# 03_Mechanicals.net
KiCad netlist of a schematic drawn in Altium Designer
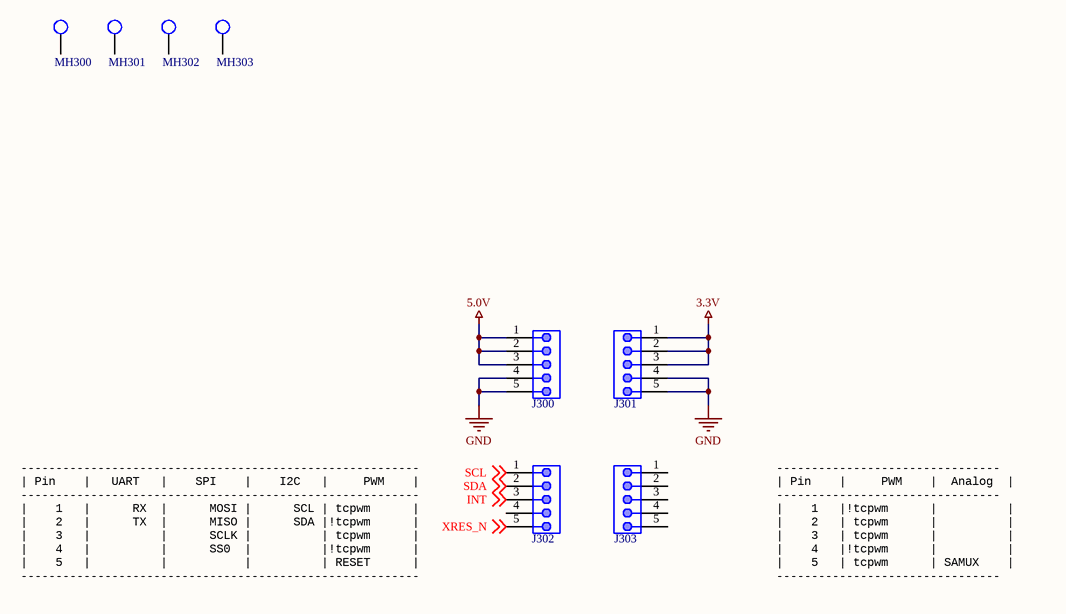
[diagram p0: 03_Mechanicals.SchDoc]

(export (version "E")
  (design (tool "Eeschema 10.0.6"))
  (components
    (comp (ref "J300")
      (value "CONN_HEADER_MALE_1x5")
      (footprint "HDR1X5")
      (description "Header, 5-Pin")
      (libsource (lib "Connectors") (part "CONN_HEADER_MALE_1x5"))
    )
    (comp (ref "J301")
      (value "CONN_HEADER_MALE_1x5")
      (footprint "HDR1X5")
      (description "Header, 5-Pin")
      (libsource (lib "") (part "CONN_HEADER_MALE_1x5_1"))
    )
    (comp (ref "J302")
      (value "CONN_HEADER_MALE_1x5")
      (footprint "HDR1X5")
      (description "Header, 5-Pin")
      (libsource (lib "Connectors") (part "CONN_HEADER_MALE_1x5"))
    )
    (comp (ref "J303")
      (value "CONN_HEADER_MALE_1x5")
      (footprint "HDR1X5")
      (description "Header, 5-Pin")
      (libsource (lib "") (part "CONN_HEADER_MALE_1x5_1"))
    )
    (comp (ref "MH300")
      (value "MHOLE_2_55MM")
      (footprint "MHOLE_2_55MM")
      (description "Mounting Holde")
      (fields (field (name "MANUFACTURER PART NUMBER") "UW MTHOLE"))
      (libsource (lib "ece315-2018-fall") (part "MHOLE_2_55MM"))
    )
    (comp (ref "MH301")
      (value "MHOLE_2_55MM")
      (footprint "MHOLE_2_55MM")
      (description "Mounting Holde")
      (fields (field (name "MANUFACTURER PART NUMBER") "UW MTHOLE"))
      (libsource (lib "ece315-2018-fall") (part "MHOLE_2_55MM"))
    )
    (comp (ref "MH302")
      (value "MHOLE_2_55MM")
      (footprint "MHOLE_2_55MM")
      (description "Mounting Holde")
      (fields (field (name "MANUFACTURER PART NUMBER") "UW MTHOLE"))
      (libsource (lib "ece315-2018-fall") (part "MHOLE_2_55MM"))
    )
    (comp (ref "MH303")
      (value "MHOLE_2_55MM")
      (footprint "MHOLE_2_55MM")
      (description "Mounting Holde")
      (fields (field (name "MANUFACTURER PART NUMBER") "UW MTHOLE"))
      (libsource (lib "ece315-2018-fall") (part "MHOLE_2_55MM"))
    )
  )
  (nets
    (net (code "1") (name "3.3V") (class "Default")
      (node (ref "J301") (pin "1") (pinfunction "1_1") (pintype "passive"))
      (node (ref "J301") (pin "2") (pinfunction "2_2") (pintype "passive"))
      (node (ref "J301") (pin "3") (pinfunction "3_3") (pintype "passive"))
    )
    (net (code "2") (name "5.0V") (class "Default")
      (node (ref "J300") (pin "1") (pinfunction "1_1") (pintype "passive"))
      (node (ref "J300") (pin "2") (pinfunction "2_2") (pintype "passive"))
      (node (ref "J300") (pin "3") (pinfunction "3_3") (pintype "passive"))
    )
    (net (code "3") (name "GND") (class "Default")
      (node (ref "J300") (pin "4") (pinfunction "4_4") (pintype "passive"))
      (node (ref "J300") (pin "5") (pinfunction "5_5") (pintype "passive"))
      (node (ref "J301") (pin "4") (pinfunction "4_4") (pintype "passive"))
      (node (ref "J301") (pin "5") (pinfunction "5_5") (pintype "passive"))
    )
    (net (code "4") (name "INT") (class "Default")
      (node (ref "J302") (pin "3") (pinfunction "3_3") (pintype "passive"))
    )
    (net (code "5") (name "SCL") (class "Default")
      (node (ref "J302") (pin "1") (pinfunction "1_1") (pintype "passive"))
    )
    (net (code "6") (name "SDA") (class "Default")
      (node (ref "J302") (pin "2") (pinfunction "2_2") (pintype "passive"))
    )
    (net (code "7") (name "XRES_N") (class "Default")
      (node (ref "J302") (pin "5") (pinfunction "5_5") (pintype "passive"))
    )
    (net (code "8") (name "unconnected-(J302-Pad4)") (class "Default")
      (node (ref "J302") (pin "4") (pinfunction "4_4") (pintype "passive"))
    )
    (net (code "9") (name "unconnected-(J303-Pad1)") (class "Default")
      (node (ref "J303") (pin "1") (pinfunction "1_1") (pintype "passive"))
    )
    (net (code "10") (name "unconnected-(J303-Pad2)") (class "Default")
      (node (ref "J303") (pin "2") (pinfunction "2_2") (pintype "passive"))
    )
    (net (code "11") (name "unconnected-(J303-Pad3)") (class "Default")
      (node (ref "J303") (pin "3") (pinfunction "3_3") (pintype "passive"))
    )
    (net (code "12") (name "unconnected-(J303-Pad4)") (class "Default")
      (node (ref "J303") (pin "4") (pinfunction "4_4") (pintype "passive"))
    )
    (net (code "13") (name "unconnected-(J303-Pad5)") (class "Default")
      (node (ref "J303") (pin "5") (pinfunction "5_5") (pintype "passive"))
    )
    (net (code "14") (name "unconnected-(MH300-Pad1)") (class "Default")
      (node (ref "MH300") (pin "1") (pintype "passive"))
    )
    (net (code "15") (name "unconnected-(MH301-Pad1)") (class "Default")
      (node (ref "MH301") (pin "1") (pintype "passive"))
    )
    (net (code "16") (name "unconnected-(MH302-Pad1)") (class "Default")
      (node (ref "MH302") (pin "1") (pintype "passive"))
    )
    (net (code "17") (name "unconnected-(MH303-Pad1)") (class "Default")
      (node (ref "MH303") (pin "1") (pintype "passive"))
    )
  )
)
